# Sheet2.net
KiCad netlist of a schematic drawn in Altium Designer
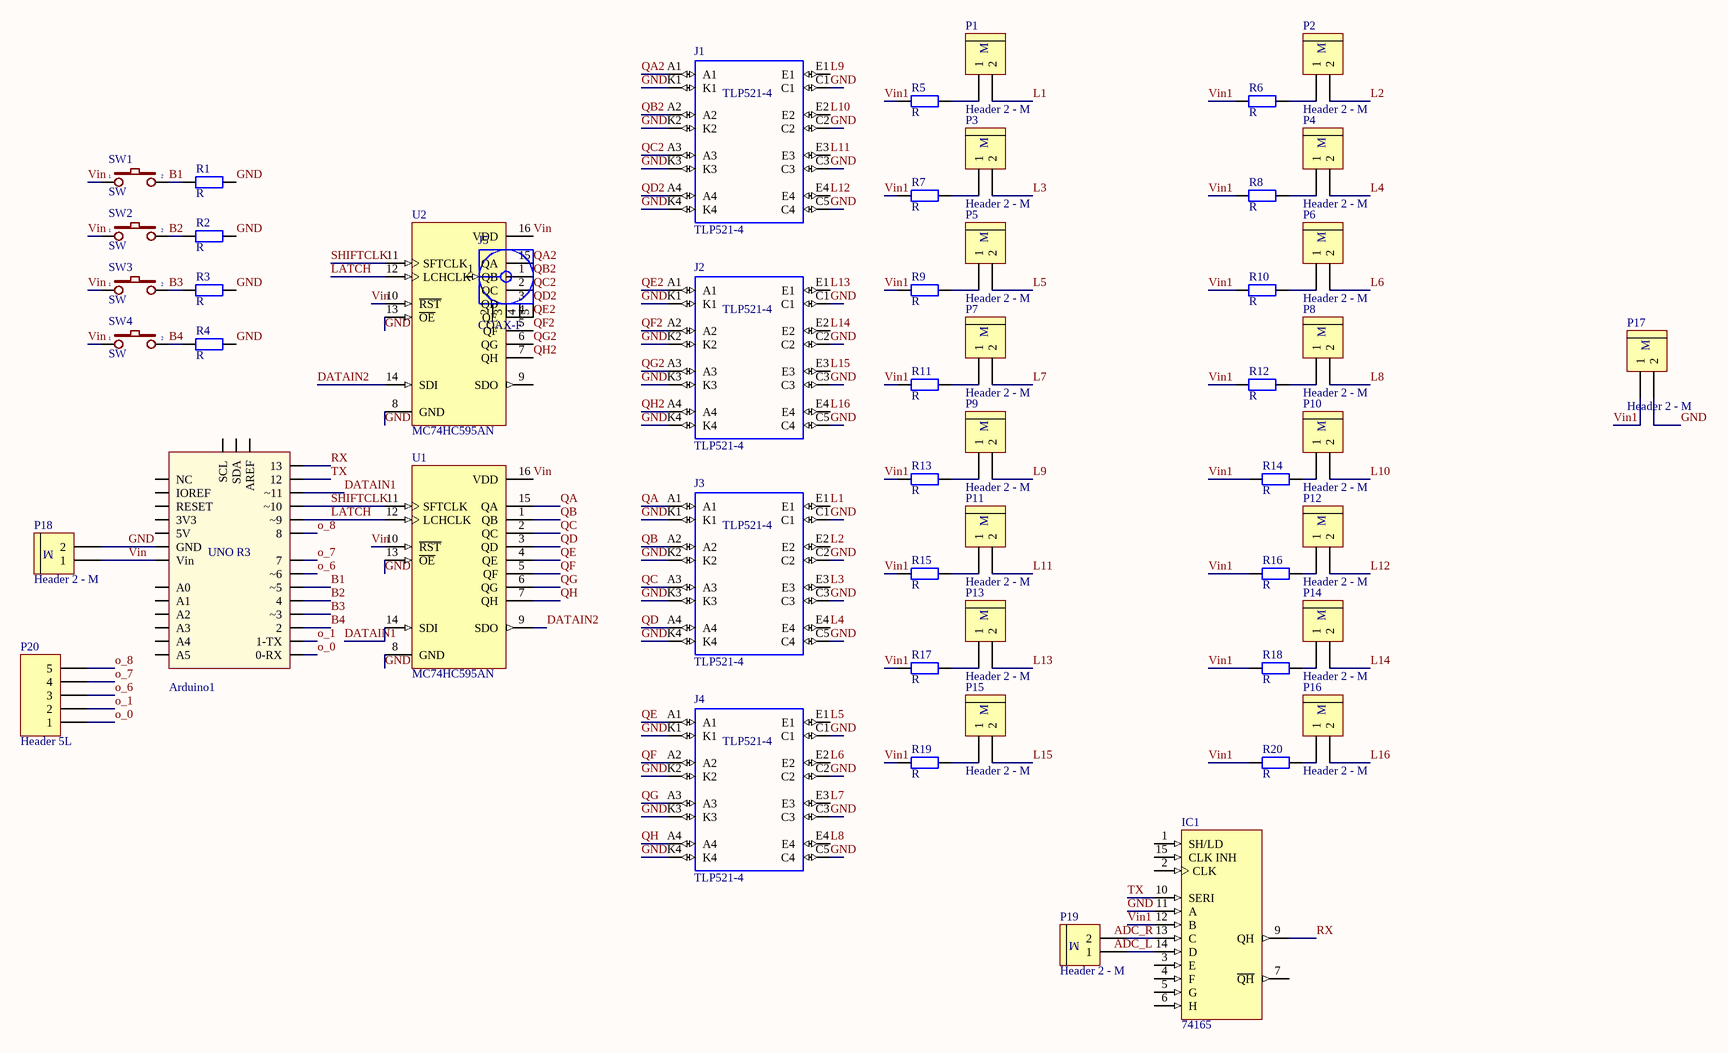
[diagram p0: Sheet2.SchDoc]

(export (version "E")
  (design (tool "Eeschema 10.0.6"))
  (components
    (comp (ref "Arduino1")
      (value "Arduino Uno R3")
      (footprint "Arduino UNO R3")
      (description "Arduino UNO R3")
      (libsource (lib "My Library") (part "Arduino Uno R3"))
    )
    (comp (ref "IC1")
      (value "74165")
      (footprint "DIP16")
      (description "8-Bit Parallel In/Serial Out Shift Register")
      (libsource (lib "adruino") (part "74165"))
    )
    (comp (ref "J1")
      (value "TLP521-4")
      (footprint "TLP521-4_FOOT")
      (description "Optoisolator Transistor Output 5300Vrms 4 Channel 16-DIP")
      (fields (field (name "MF") "Isocom Components") (field (name "DIGI-KEY_PART_NUMBER") "TLP521-4X-ND"))
      (libsource (lib "TLP521-4") (part "TLP521-4"))
    )
    (comp (ref "J2")
      (value "TLP521-4")
      (footprint "TLP521-4_FOOT")
      (description "Optoisolator Transistor Output 5300Vrms 4 Channel 16-DIP")
      (fields (field (name "MF") "Isocom Components") (field (name "DIGI-KEY_PART_NUMBER") "TLP521-4X-ND"))
      (libsource (lib "TLP521-4") (part "TLP521-4"))
    )
    (comp (ref "J3")
      (value "TLP521-4")
      (footprint "TLP521-4_FOOT")
      (description "Optoisolator Transistor Output 5300Vrms 4 Channel 16-DIP")
      (fields (field (name "MF") "Isocom Components") (field (name "DIGI-KEY_PART_NUMBER") "TLP521-4X-ND"))
      (libsource (lib "TLP521-4") (part "TLP521-4"))
    )
    (comp (ref "J4")
      (value "TLP521-4")
      (footprint "TLP521-4_FOOT")
      (description "Optoisolator Transistor Output 5300Vrms 4 Channel 16-DIP")
      (fields (field (name "MF") "Isocom Components") (field (name "DIGI-KEY_PART_NUMBER") "TLP521-4X-ND"))
      (libsource (lib "TLP521-4") (part "TLP521-4"))
    )
    (comp (ref "J5")
      (value "COAX-F")
      (footprint "heromap:MCX5.08-H5")
      (fields (field (name "PUBLISHER") "Altium Limited"))
      (libsource (lib "adruino") (part "COAX-F"))
    )
    (comp (ref "P1")
      (value "Header 2 - M")
      (footprint "Medium - Header 2")
      (description "Header, 2-Pin, Medium")
      (fields (field (name "PUBLISHER") "Altium Limited"))
      (libsource (lib "adruino") (part "Header 2 - M"))
    )
    (comp (ref "P2")
      (value "Header 2 - M")
      (footprint "Medium - Header 2")
      (description "Header, 2-Pin, Medium")
      (fields (field (name "PUBLISHER") "Altium Limited"))
      (libsource (lib "adruino") (part "Header 2 - M"))
    )
    (comp (ref "P3")
      (value "Header 2 - M")
      (footprint "Medium - Header 2")
      (description "Header, 2-Pin, Medium")
      (fields (field (name "PUBLISHER") "Altium Limited"))
      (libsource (lib "adruino") (part "Header 2 - M"))
    )
    (comp (ref "P4")
      (value "Header 2 - M")
      (footprint "Medium - Header 2")
      (description "Header, 2-Pin, Medium")
      (fields (field (name "PUBLISHER") "Altium Limited"))
      (libsource (lib "adruino") (part "Header 2 - M"))
    )
    (comp (ref "P5")
      (value "Header 2 - M")
      (footprint "Medium - Header 2")
      (description "Header, 2-Pin, Medium")
      (fields (field (name "PUBLISHER") "Altium Limited"))
      (libsource (lib "adruino") (part "Header 2 - M"))
    )
    (comp (ref "P6")
      (value "Header 2 - M")
      (footprint "Medium - Header 2")
      (description "Header, 2-Pin, Medium")
      (fields (field (name "PUBLISHER") "Altium Limited"))
      (libsource (lib "adruino") (part "Header 2 - M"))
    )
    (comp (ref "P7")
      (value "Header 2 - M")
      (footprint "Medium - Header 2")
      (description "Header, 2-Pin, Medium")
      (fields (field (name "PUBLISHER") "Altium Limited"))
      (libsource (lib "adruino") (part "Header 2 - M"))
    )
    (comp (ref "P8")
      (value "Header 2 - M")
      (footprint "Medium - Header 2")
      (description "Header, 2-Pin, Medium")
      (fields (field (name "PUBLISHER") "Altium Limited"))
      (libsource (lib "adruino") (part "Header 2 - M"))
    )
    (comp (ref "P9")
      (value "Header 2 - M")
      (footprint "Medium - Header 2")
      (description "Header, 2-Pin, Medium")
      (fields (field (name "PUBLISHER") "Altium Limited"))
      (libsource (lib "adruino") (part "Header 2 - M"))
    )
    (comp (ref "P10")
      (value "Header 2 - M")
      (footprint "Medium - Header 2")
      (description "Header, 2-Pin, Medium")
      (fields (field (name "PUBLISHER") "Altium Limited"))
      (libsource (lib "adruino") (part "Header 2 - M"))
    )
    (comp (ref "P11")
      (value "Header 2 - M")
      (footprint "Medium - Header 2")
      (description "Header, 2-Pin, Medium")
      (fields (field (name "PUBLISHER") "Altium Limited"))
      (libsource (lib "adruino") (part "Header 2 - M"))
    )
    (comp (ref "P12")
      (value "Header 2 - M")
      (footprint "Medium - Header 2")
      (description "Header, 2-Pin, Medium")
      (fields (field (name "PUBLISHER") "Altium Limited"))
      (libsource (lib "adruino") (part "Header 2 - M"))
    )
    (comp (ref "P13")
      (value "Header 2 - M")
      (footprint "Medium - Header 2")
      (description "Header, 2-Pin, Medium")
      (fields (field (name "PUBLISHER") "Altium Limited"))
      (libsource (lib "adruino") (part "Header 2 - M"))
    )
    (comp (ref "P14")
      (value "Header 2 - M")
      (footprint "Medium - Header 2")
      (description "Header, 2-Pin, Medium")
      (fields (field (name "PUBLISHER") "Altium Limited"))
      (libsource (lib "adruino") (part "Header 2 - M"))
    )
    (comp (ref "P15")
      (value "Header 2 - M")
      (footprint "Medium - Header 2")
      (description "Header, 2-Pin, Medium")
      (fields (field (name "PUBLISHER") "Altium Limited"))
      (libsource (lib "adruino") (part "Header 2 - M"))
    )
    (comp (ref "P16")
      (value "Header 2 - M")
      (footprint "Medium - Header 2")
      (description "Header, 2-Pin, Medium")
      (fields (field (name "PUBLISHER") "Altium Limited"))
      (libsource (lib "adruino") (part "Header 2 - M"))
    )
    (comp (ref "P17")
      (value "Header 2 - M")
      (footprint "Medium - Header 2")
      (description "Header, 2-Pin, Medium")
      (fields (field (name "PUBLISHER") "Altium Limited"))
      (libsource (lib "adruino") (part "Header 2 - M"))
    )
    (comp (ref "P18")
      (value "Header 2 - M")
      (footprint "Medium - Header 2")
      (description "Header, 2-Pin, Medium")
      (fields (field (name "PUBLISHER") "Altium Limited"))
      (libsource (lib "") (part "Header 2 - M_1"))
    )
    (comp (ref "P19")
      (value "Header 2 - M")
      (footprint "Medium - Header 2")
      (description "Header, 2-Pin, Medium")
      (fields (field (name "PUBLISHER") "Altium Limited"))
      (libsource (lib "") (part "Header 2 - M_1"))
    )
    (comp (ref "P20")
      (value "Header 5L")
      (footprint "HDR1X5 - L")
      (description "Header, 5-Pin")
      (fields (field (name "PUBLISHER") "Altium Limited"))
      (libsource (lib "adruino") (part "Header 5L"))
    )
    (comp (ref "R1")
      (value "R")
      (footprint "DIEN TRO 1/4 W")
      (description "Resistor")
      (fields (field (name "Comment") "R0.4W") (field (name "PUBLISHER") "Altium Limited"))
      (libsource (lib "adruino") (part "Res 1/4 W"))
    )
    (comp (ref "R2")
      (value "R")
      (footprint "DIEN TRO 1/4 W")
      (description "Resistor")
      (fields (field (name "Comment") "R0.4W") (field (name "PUBLISHER") "Altium Limited"))
      (libsource (lib "adruino") (part "Res 1/4 W"))
    )
    (comp (ref "R3")
      (value "R")
      (footprint "DIEN TRO 1/4 W")
      (description "Resistor")
      (fields (field (name "Comment") "R0.4W") (field (name "PUBLISHER") "Altium Limited"))
      (libsource (lib "adruino") (part "Res 1/4 W"))
    )
    (comp (ref "R4")
      (value "R")
      (footprint "DIEN TRO 1/4 W")
      (description "Resistor")
      (fields (field (name "Comment") "R0.4W") (field (name "PUBLISHER") "Altium Limited"))
      (libsource (lib "adruino") (part "Res 1/4 W"))
    )
    (comp (ref "R5")
      (value "R")
      (footprint "DIEN TRO 1/4 W")
      (description "Resistor")
      (fields (field (name "Comment") "R0.4W") (field (name "PUBLISHER") "Altium Limited"))
      (libsource (lib "adruino") (part "Res 1/4 W"))
    )
    (comp (ref "R6")
      (value "R")
      (footprint "DIEN TRO 1/4 W")
      (description "Resistor")
      (fields (field (name "Comment") "R0.4W") (field (name "PUBLISHER") "Altium Limited"))
      (libsource (lib "adruino") (part "Res 1/4 W"))
    )
    (comp (ref "R7")
      (value "R")
      (footprint "DIEN TRO 1/4 W")
      (description "Resistor")
      (fields (field (name "Comment") "R0.4W") (field (name "PUBLISHER") "Altium Limited"))
      (libsource (lib "adruino") (part "Res 1/4 W"))
    )
    (comp (ref "R8")
      (value "R")
      (footprint "DIEN TRO 1/4 W")
      (description "Resistor")
      (fields (field (name "Comment") "R0.4W") (field (name "PUBLISHER") "Altium Limited"))
      (libsource (lib "adruino") (part "Res 1/4 W"))
    )
    (comp (ref "R9")
      (value "R")
      (footprint "DIEN TRO 1/4 W")
      (description "Resistor")
      (fields (field (name "Comment") "R0.4W") (field (name "PUBLISHER") "Altium Limited"))
      (libsource (lib "adruino") (part "Res 1/4 W"))
    )
    (comp (ref "R10")
      (value "R")
      (footprint "DIEN TRO 1/4 W")
      (description "Resistor")
      (fields (field (name "Comment") "R0.4W") (field (name "PUBLISHER") "Altium Limited"))
      (libsource (lib "adruino") (part "Res 1/4 W"))
    )
    (comp (ref "R11")
      (value "R")
      (footprint "DIEN TRO 1/4 W")
      (description "Resistor")
      (fields (field (name "Comment") "R0.4W") (field (name "PUBLISHER") "Altium Limited"))
      (libsource (lib "adruino") (part "Res 1/4 W"))
    )
    (comp (ref "R12")
      (value "R")
      (footprint "DIEN TRO 1/4 W")
      (description "Resistor")
      (fields (field (name "Comment") "R0.4W") (field (name "PUBLISHER") "Altium Limited"))
      (libsource (lib "adruino") (part "Res 1/4 W"))
    )
    (comp (ref "R13")
      (value "R")
      (footprint "DIEN TRO 1/4 W")
      (description "Resistor")
      (fields (field (name "Comment") "R0.4W") (field (name "PUBLISHER") "Altium Limited"))
      (libsource (lib "adruino") (part "Res 1/4 W"))
    )
    (comp (ref "R14")
      (value "R")
      (footprint "DIEN TRO 1/4 W")
      (description "Resistor")
      (fields (field (name "Comment") "R0.4W") (field (name "PUBLISHER") "Altium Limited"))
      (libsource (lib "adruino") (part "Res 1/4 W"))
    )
    (comp (ref "R15")
      (value "R")
      (footprint "DIEN TRO 1/4 W")
      (description "Resistor")
      (fields (field (name "Comment") "R0.4W") (field (name "PUBLISHER") "Altium Limited"))
      (libsource (lib "adruino") (part "Res 1/4 W"))
    )
    (comp (ref "R16")
      (value "R")
      (footprint "DIEN TRO 1/4 W")
      (description "Resistor")
      (fields (field (name "Comment") "R0.4W") (field (name "PUBLISHER") "Altium Limited"))
      (libsource (lib "adruino") (part "Res 1/4 W"))
    )
    (comp (ref "R17")
      (value "R")
      (footprint "DIEN TRO 1/4 W")
      (description "Resistor")
      (fields (field (name "Comment") "R0.4W") (field (name "PUBLISHER") "Altium Limited"))
      (libsource (lib "adruino") (part "Res 1/4 W"))
    )
    (comp (ref "R18")
      (value "R")
      (footprint "DIEN TRO 1/4 W")
      (description "Resistor")
      (fields (field (name "Comment") "R0.4W") (field (name "PUBLISHER") "Altium Limited"))
      (libsource (lib "adruino") (part "Res 1/4 W"))
    )
    (comp (ref "R19")
      (value "R")
      (footprint "DIEN TRO 1/4 W")
      (description "Resistor")
      (fields (field (name "Comment") "R0.4W") (field (name "PUBLISHER") "Altium Limited"))
      (libsource (lib "adruino") (part "Res 1/4 W"))
    )
    (comp (ref "R20")
      (value "R")
      (footprint "DIEN TRO 1/4 W")
      (description "Resistor")
      (fields (field (name "Comment") "R0.4W") (field (name "PUBLISHER") "Altium Limited"))
      (libsource (lib "adruino") (part "Res 1/4 W"))
    )
    (comp (ref "SW1")
      (value "SW")
      (footprint "SW2")
      (description "Switch button 2 pin")
      (libsource (lib "adruino") (part "SW2"))
    )
    (comp (ref "SW2")
      (value "SW")
      (footprint "SW2")
      (description "Switch button 2 pin")
      (libsource (lib "adruino") (part "SW2"))
    )
    (comp (ref "SW3")
      (value "SW")
      (footprint "SW2")
      (description "Switch button 2 pin")
      (libsource (lib "adruino") (part "SW2"))
    )
    (comp (ref "SW4")
      (value "SW")
      (footprint "SW2")
      (description "Switch button 2 pin")
      (libsource (lib "adruino") (part "SW2"))
    )
    (comp (ref "U1")
      (value "MC74HC595AN")
      (footprint "DIP.100/16/W.300/L.900")
      (description "8-Bit Serial-Input/Serial or Prallel-Output Shift Register with Latched 3-State Outputs")
      (fields (field (name "PUBLISHER") "Altium Limited"))
      (libsource (lib "adruino") (part "MC74HC595AN"))
    )
    (comp (ref "U2")
      (value "MC74HC595AN")
      (footprint "DIP.100/16/W.300/L.900")
      (description "8-Bit Serial-Input/Serial or Prallel-Output Shift Register with Latched 3-State Outputs")
      (fields (field (name "PUBLISHER") "Altium Limited"))
      (libsource (lib "adruino") (part "MC74HC595AN"))
    )
  )
  (nets
    (net (code "3") (name "/B1") (class "Default")
      (node (ref "Arduino1") (pin "~5") (pinfunction "~5_~5") (pintype "passive"))
      (node (ref "R1") (pin "1") (pinfunction "1_1") (pintype "passive"))
      (node (ref "SW1") (pin "2") (pinfunction "2_2") (pintype "passive"))
    )
    (net (code "4") (name "/B2") (class "Default")
      (node (ref "Arduino1") (pin "4") (pinfunction "4_4") (pintype "passive"))
      (node (ref "R2") (pin "1") (pinfunction "1_1") (pintype "passive"))
      (node (ref "SW2") (pin "2") (pinfunction "2_2") (pintype "passive"))
    )
    (net (code "5") (name "/B3") (class "Default")
      (node (ref "Arduino1") (pin "~3") (pinfunction "~3_~3") (pintype "passive"))
      (node (ref "R3") (pin "1") (pinfunction "1_1") (pintype "passive"))
      (node (ref "SW3") (pin "2") (pinfunction "2_2") (pintype "passive"))
    )
    (net (code "6") (name "/B4") (class "Default")
      (node (ref "Arduino1") (pin "2") (pinfunction "2_2") (pintype "passive"))
      (node (ref "R4") (pin "1") (pinfunction "1_1") (pintype "passive"))
      (node (ref "SW4") (pin "2") (pinfunction "2_2") (pintype "passive"))
    )
    (net (code "7") (name "/DATAIN1") (class "Default")
      (node (ref "Arduino1") (pin "~11") (pinfunction "~11_~11") (pintype "passive"))
      (node (ref "U1") (pin "14") (pinfunction "SDI_14") (pintype "input"))
    )
    (net (code "8") (name "/DATAIN2") (class "Default")
      (node (ref "U1") (pin "9") (pinfunction "SDO_9") (pintype "output"))
      (node (ref "U2") (pin "14") (pinfunction "SDI_14") (pintype "input"))
    )
    (net (code "9") (name "/L1") (class "Default")
      (node (ref "J3") (pin "E1") (pinfunction "E1_E1") (pintype "bidirectional"))
      (node (ref "P1") (pin "2") (pinfunction "2_2") (pintype "passive"))
    )
    (net (code "10") (name "/L2") (class "Default")
      (node (ref "J3") (pin "E2") (pinfunction "E2_E2") (pintype "bidirectional"))
      (node (ref "P2") (pin "2") (pinfunction "2_2") (pintype "passive"))
    )
    (net (code "11") (name "/L3") (class "Default")
      (node (ref "J3") (pin "E3") (pinfunction "E3_E3") (pintype "bidirectional"))
      (node (ref "P3") (pin "2") (pinfunction "2_2") (pintype "passive"))
    )
    (net (code "12") (name "/L4") (class "Default")
      (node (ref "J3") (pin "E4") (pinfunction "E4_E4") (pintype "bidirectional"))
      (node (ref "P4") (pin "2") (pinfunction "2_2") (pintype "passive"))
    )
    (net (code "13") (name "/L5") (class "Default")
      (node (ref "J4") (pin "E1") (pinfunction "E1_E1") (pintype "bidirectional"))
      (node (ref "P5") (pin "2") (pinfunction "2_2") (pintype "passive"))
    )
    (net (code "14") (name "/L6") (class "Default")
      (node (ref "J4") (pin "E2") (pinfunction "E2_E2") (pintype "bidirectional"))
      (node (ref "P6") (pin "2") (pinfunction "2_2") (pintype "passive"))
    )
    (net (code "15") (name "/L7") (class "Default")
      (node (ref "J4") (pin "E3") (pinfunction "E3_E3") (pintype "bidirectional"))
      (node (ref "P7") (pin "2") (pinfunction "2_2") (pintype "passive"))
    )
    (net (code "16") (name "/L8") (class "Default")
      (node (ref "J4") (pin "E4") (pinfunction "E4_E4") (pintype "bidirectional"))
      (node (ref "P8") (pin "2") (pinfunction "2_2") (pintype "passive"))
    )
    (net (code "17") (name "/L9") (class "Default")
      (node (ref "J1") (pin "E1") (pinfunction "E1_E1") (pintype "bidirectional"))
      (node (ref "P9") (pin "2") (pinfunction "2_2") (pintype "passive"))
    )
    (net (code "18") (name "/L10") (class "Default")
      (node (ref "J1") (pin "E2") (pinfunction "E2_E2") (pintype "bidirectional"))
      (node (ref "P10") (pin "2") (pinfunction "2_2") (pintype "passive"))
    )
    (net (code "19") (name "/L11") (class "Default")
      (node (ref "J1") (pin "E3") (pinfunction "E3_E3") (pintype "bidirectional"))
      (node (ref "P11") (pin "2") (pinfunction "2_2") (pintype "passive"))
    )
    (net (code "20") (name "/L12") (class "Default")
      (node (ref "J1") (pin "E4") (pinfunction "E4_E4") (pintype "bidirectional"))
      (node (ref "P12") (pin "2") (pinfunction "2_2") (pintype "passive"))
    )
    (net (code "21") (name "/L13") (class "Default")
      (node (ref "J2") (pin "E1") (pinfunction "E1_E1") (pintype "bidirectional"))
      (node (ref "P13") (pin "2") (pinfunction "2_2") (pintype "passive"))
    )
    (net (code "22") (name "/L14") (class "Default")
      (node (ref "J2") (pin "E2") (pinfunction "E2_E2") (pintype "bidirectional"))
      (node (ref "P14") (pin "2") (pinfunction "2_2") (pintype "passive"))
    )
    (net (code "23") (name "/L15") (class "Default")
      (node (ref "J2") (pin "E3") (pinfunction "E3_E3") (pintype "bidirectional"))
      (node (ref "P15") (pin "2") (pinfunction "2_2") (pintype "passive"))
    )
    (net (code "24") (name "/L16") (class "Default")
      (node (ref "J2") (pin "E4") (pinfunction "E4_E4") (pintype "bidirectional"))
      (node (ref "P16") (pin "2") (pinfunction "2_2") (pintype "passive"))
    )
    (net (code "25") (name "/LATCH") (class "Default")
      (node (ref "Arduino1") (pin "~9") (pinfunction "~9_~9") (pintype "passive"))
      (node (ref "U1") (pin "12") (pinfunction "LCHCLK_12") (pintype "input"))
      (node (ref "U2") (pin "12") (pinfunction "LCHCLK_12") (pintype "input"))
    )
    (net (code "26") (name "/QA") (class "Default")
      (node (ref "J3") (pin "A1") (pinfunction "A1_A1") (pintype "bidirectional"))
      (node (ref "U1") (pin "15") (pinfunction "QA_15") (pintype "tri_state"))
    )
    (net (code "27") (name "/QA2") (class "Default")
      (node (ref "J1") (pin "A1") (pinfunction "A1_A1") (pintype "bidirectional"))
      (node (ref "U2") (pin "15") (pinfunction "QA_15") (pintype "tri_state"))
    )
    (net (code "28") (name "/QB") (class "Default")
      (node (ref "J3") (pin "A2") (pinfunction "A2_A2") (pintype "bidirectional"))
      (node (ref "U1") (pin "1") (pinfunction "QB_1") (pintype "tri_state"))
    )
    (net (code "29") (name "/QB2") (class "Default")
      (node (ref "J1") (pin "A2") (pinfunction "A2_A2") (pintype "bidirectional"))
      (node (ref "U2") (pin "1") (pinfunction "QB_1") (pintype "tri_state"))
    )
    (net (code "30") (name "/QC") (class "Default")
      (node (ref "J3") (pin "A3") (pinfunction "A3_A3") (pintype "bidirectional"))
      (node (ref "U1") (pin "2") (pinfunction "QC_2") (pintype "tri_state"))
    )
    (net (code "31") (name "/QC2") (class "Default")
      (node (ref "J1") (pin "A3") (pinfunction "A3_A3") (pintype "bidirectional"))
      (node (ref "U2") (pin "2") (pinfunction "QC_2") (pintype "tri_state"))
    )
    (net (code "32") (name "/QD") (class "Default")
      (node (ref "J3") (pin "A4") (pinfunction "A4_A4") (pintype "bidirectional"))
      (node (ref "U1") (pin "3") (pinfunction "QD_3") (pintype "tri_state"))
    )
    (net (code "33") (name "/QD2") (class "Default")
      (node (ref "J1") (pin "A4") (pinfunction "A4_A4") (pintype "bidirectional"))
      (node (ref "U2") (pin "3") (pinfunction "QD_3") (pintype "tri_state"))
    )
    (net (code "34") (name "/QE") (class "Default")
      (node (ref "J4") (pin "A1") (pinfunction "A1_A1") (pintype "bidirectional"))
      (node (ref "U1") (pin "4") (pinfunction "QE_4") (pintype "tri_state"))
    )
    (net (code "35") (name "/QE2") (class "Default")
      (node (ref "J2") (pin "A1") (pinfunction "A1_A1") (pintype "bidirectional"))
      (node (ref "J5") (pin "5") (pinfunction "GND_5") (pintype "power_in"))
      (node (ref "U2") (pin "4") (pinfunction "QE_4") (pintype "tri_state"))
    )
    (net (code "36") (name "/QF") (class "Default")
      (node (ref "J4") (pin "A2") (pinfunction "A2_A2") (pintype "bidirectional"))
      (node (ref "U1") (pin "5") (pinfunction "QF_5") (pintype "tri_state"))
    )
    (net (code "37") (name "/QF2") (class "Default")
      (node (ref "J2") (pin "A2") (pinfunction "A2_A2") (pintype "bidirectional"))
      (node (ref "U2") (pin "5") (pinfunction "QF_5") (pintype "tri_state"))
    )
    (net (code "38") (name "/QG") (class "Default")
      (node (ref "J4") (pin "A3") (pinfunction "A3_A3") (pintype "bidirectional"))
      (node (ref "U1") (pin "6") (pinfunction "QG_6") (pintype "tri_state"))
    )
    (net (code "39") (name "/QG2") (class "Default")
      (node (ref "J2") (pin "A3") (pinfunction "A3_A3") (pintype "bidirectional"))
      (node (ref "U2") (pin "6") (pinfunction "QG_6") (pintype "tri_state"))
    )
    (net (code "40") (name "/QH") (class "Default")
      (node (ref "J4") (pin "A4") (pinfunction "A4_A4") (pintype "bidirectional"))
      (node (ref "U1") (pin "7") (pinfunction "QH_7") (pintype "tri_state"))
    )
    (net (code "41") (name "/QH2") (class "Default")
      (node (ref "J2") (pin "A4") (pinfunction "A4_A4") (pintype "bidirectional"))
      (node (ref "U2") (pin "7") (pinfunction "QH_7") (pintype "tri_state"))
    )
    (net (code "42") (name "/RX") (class "Default")
      (node (ref "Arduino1") (pin "13") (pinfunction "13_13") (pintype "passive"))
      (node (ref "IC1") (pin "9") (pinfunction "QH_9") (pintype "output"))
    )
    (net (code "43") (name "/SHIFTCLK") (class "Default")
      (node (ref "Arduino1") (pin "~10") (pinfunction "~10_~10") (pintype "passive"))
      (node (ref "U1") (pin "11") (pinfunction "SFTCLK_11") (pintype "input"))
      (node (ref "U2") (pin "11") (pinfunction "SFTCLK_11") (pintype "input"))
    )
    (net (code "44") (name "/TX") (class "Default")
      (node (ref "Arduino1") (pin "12") (pinfunction "12_12") (pintype "passive"))
      (node (ref "IC1") (pin "10") (pinfunction "SERI_10") (pintype "input"))
    )
    (net (code "45") (name "/Vin") (class "Default")
      (node (ref "Arduino1") (pin "Vin") (pinfunction "Vin_Vin") (pintype "passive"))
      (node (ref "P18") (pin "1") (pinfunction "1_1") (pintype "passive"))
      (node (ref "SW1") (pin "1") (pinfunction "1_1") (pintype "passive"))
      (node (ref "SW2") (pin "1") (pinfunction "1_1") (pintype "passive"))
      (node (ref "SW3") (pin "1") (pinfunction "1_1") (pintype "passive"))
      (node (ref "SW4") (pin "1") (pinfunction "1_1") (pintype "passive"))
      (node (ref "U1") (pin "10") (pinfunction "~{RST}_10") (pintype "input"))
      (node (ref "U1") (pin "16") (pinfunction "VDD_16") (pintype "power_in"))
      (node (ref "U2") (pin "10") (pinfunction "~{RST}_10") (pintype "input"))
      (node (ref "U2") (pin "16") (pinfunction "VDD_16") (pintype "power_in"))
    )
    (net (code "46") (name "/Vin1") (class "Default")
      (node (ref "IC1") (pin "12") (pinfunction "B_12") (pintype "input"))
      (node (ref "P17") (pin "1") (pinfunction "1_1") (pintype "passive"))
      (node (ref "R10") (pin "1") (pinfunction "1_1") (pintype "passive"))
      (node (ref "R11") (pin "1") (pinfunction "1_1") (pintype "passive"))
      (node (ref "R12") (pin "1") (pinfunction "1_1") (pintype "passive"))
      (node (ref "R13") (pin "1") (pinfunction "1_1") (pintype "passive"))
      (node (ref "R14") (pin "1") (pinfunction "1_1") (pintype "passive"))
      (node (ref "R15") (pin "1") (pinfunction "1_1") (pintype "passive"))
      (node (ref "R16") (pin "1") (pinfunction "1_1") (pintype "passive"))
      (node (ref "R17") (pin "1") (pinfunction "1_1") (pintype "passive"))
      (node (ref "R18") (pin "1") (pinfunction "1_1") (pintype "passive"))
      (node (ref "R19") (pin "1") (pinfunction "1_1") (pintype "passive"))
      (node (ref "R20") (pin "1") (pinfunction "1_1") (pintype "passive"))
      (node (ref "R5") (pin "1") (pinfunction "1_1") (pintype "passive"))
      (node (ref "R6") (pin "1") (pinfunction "1_1") (pintype "passive"))
      (node (ref "R7") (pin "1") (pinfunction "1_1") (pintype "passive"))
      (node (ref "R8") (pin "1") (pinfunction "1_1") (pintype "passive"))
      (node (ref "R9") (pin "1") (pinfunction "1_1") (pintype "passive"))
    )
    (net (code "47") (name "/o_0") (class "Default")
      (node (ref "Arduino1") (pin "0-RX") (pinfunction "0-RX_0-RX") (pintype "passive"))
      (node (ref "P20") (pin "1") (pinfunction "1_1") (pintype "passive"))
    )
    (net (code "48") (name "/o_1") (class "Default")
      (node (ref "Arduino1") (pin "1-TX") (pinfunction "1-TX_1-TX") (pintype "passive"))
      (node (ref "P20") (pin "2") (pinfunction "2_2") (pintype "passive"))
    )
    (net (code "49") (name "/o_6") (class "Default")
      (node (ref "Arduino1") (pin "~6") (pinfunction "~6_~6") (pintype "passive"))
      (node (ref "P20") (pin "3") (pinfunction "3_3") (pintype "passive"))
    )
    (net (code "50") (name "/o_7") (class "Default")
      (node (ref "Arduino1") (pin "7") (pinfunction "7_7") (pintype "passive"))
      (node (ref "P20") (pin "4") (pinfunction "4_4") (pintype "passive"))
    )
    (net (code "51") (name "/o_8") (class "Default")
      (node (ref "Arduino1") (pin "8") (pinfunction "8_8") (pintype "passive"))
      (node (ref "P20") (pin "5") (pinfunction "5_5") (pintype "passive"))
    )
    (net (code "52") (name "GND") (class "Default")
      (node (ref "Arduino1") (pin "GND") (pinfunction "GND_GND") (pintype "passive"))
      (node (ref "IC1") (pin "11") (pinfunction "A_11") (pintype "input"))
      (node (ref "IC1") (pin "8") (pinfunction "GND_8") (pintype "power_in"))
      (node (ref "J1") (pin "C1") (pinfunction "C1_C1") (pintype "bidirectional"))
      (node (ref "J1") (pin "C2") (pinfunction "C2_C2") (pintype "bidirectional"))
      (node (ref "J1") (pin "C3") (pinfunction "C3_C3") (pintype "bidirectional"))
      (node (ref "J1") (pin "C5") (pinfunction "C4_C5") (pintype "bidirectional"))
      (node (ref "J1") (pin "K1") (pinfunction "K1_K1") (pintype "bidirectional"))
      (node (ref "J1") (pin "K2") (pinfunction "K2_K2") (pintype "bidirectional"))
      (node (ref "J1") (pin "K3") (pinfunction "K3_K3") (pintype "bidirectional"))
      (node (ref "J1") (pin "K4") (pinfunction "K4_K4") (pintype "bidirectional"))
      (node (ref "J2") (pin "C1") (pinfunction "C1_C1") (pintype "bidirectional"))
      (node (ref "J2") (pin "C2") (pinfunction "C2_C2") (pintype "bidirectional"))
      (node (ref "J2") (pin "C3") (pinfunction "C3_C3") (pintype "bidirectional"))
      (node (ref "J2") (pin "C5") (pinfunction "C4_C5") (pintype "bidirectional"))
      (node (ref "J2") (pin "K1") (pinfunction "K1_K1") (pintype "bidirectional"))
      (node (ref "J2") (pin "K2") (pinfunction "K2_K2") (pintype "bidirectional"))
      (node (ref "J2") (pin "K3") (pinfunction "K3_K3") (pintype "bidirectional"))
      (node (ref "J2") (pin "K4") (pinfunction "K4_K4") (pintype "bidirectional"))
      (node (ref "J3") (pin "C1") (pinfunction "C1_C1") (pintype "bidirectional"))
      (node (ref "J3") (pin "C2") (pinfunction "C2_C2") (pintype "bidirectional"))
      (node (ref "J3") (pin "C3") (pinfunction "C3_C3") (pintype "bidirectional"))
      (node (ref "J3") (pin "C5") (pinfunction "C4_C5") (pintype "bidirectional"))
      (node (ref "J3") (pin "K1") (pinfunction "K1_K1") (pintype "bidirectional"))
      (node (ref "J3") (pin "K2") (pinfunction "K2_K2") (pintype "bidirectional"))
      (node (ref "J3") (pin "K3") (pinfunction "K3_K3") (pintype "bidirectional"))
      (node (ref "J3") (pin "K4") (pinfunction "K4_K4") (pintype "bidirectional"))
      (node (ref "J4") (pin "C1") (pinfunction "C1_C1") (pintype "bidirectional"))
      (node (ref "J4") (pin "C2") (pinfunction "C2_C2") (pintype "bidirectional"))
      (node (ref "J4") (pin "C3") (pinfunction "C3_C3") (pintype "bidirectional"))
      (node (ref "J4") (pin "C5") (pinfunction "C4_C5") (pintype "bidirectional"))
      (node (ref "J4") (pin "K1") (pinfunction "K1_K1") (pintype "bidirectional"))
      (node (ref "J4") (pin "K2") (pinfunction "K2_K2") (pintype "bidirectional"))
      (node (ref "J4") (pin "K3") (pinfunction "K3_K3") (pintype "bidirectional"))
      (node (ref "J4") (pin "K4") (pinfunction "K4_K4") (pintype "bidirectional"))
      (node (ref "P17") (pin "2") (pinfunction "2_2") (pintype "passive"))
      (node (ref "P18") (pin "2") (pinfunction "2_2") (pintype "passive"))
      (node (ref "R1") (pin "2") (pinfunction "2_2") (pintype "passive"))
      (node (ref "R2") (pin "2") (pinfunction "2_2") (pintype "passive"))
      (node (ref "R3") (pin "2") (pinfunction "2_2") (pintype "passive"))
      (node (ref "R4") (pin "2") (pinfunction "2_2") (pintype "passive"))
      (node (ref "U1") (pin "13") (pinfunction "~{OE}_13") (pintype "input"))
      (node (ref "U1") (pin "8") (pinfunction "GND_8") (pintype "power_in"))
      (node (ref "U2") (pin "13") (pinfunction "~{OE}_13") (pintype "input"))
      (node (ref "U2") (pin "8") (pinfunction "GND_8") (pintype "power_in"))
    )
    (net (code "53") (name "Net-(IC1-C)") (class "Default")
      (node (ref "IC1") (pin "13") (pinfunction "C_13") (pintype "input"))
      (node (ref "P19") (pin "2") (pinfunction "2_2") (pintype "passive"))
    )
    (net (code "54") (name "Net-(IC1-D)") (class "Default")
      (node (ref "IC1") (pin "14") (pinfunction "D_14") (pintype "input"))
      (node (ref "P19") (pin "1") (pinfunction "1_1") (pintype "passive"))
    )
    (net (code "55") (name "Net-(P1-Pad1)") (class "Default")
      (node (ref "P1") (pin "1") (pinfunction "1_1") (pintype "passive"))
      (node (ref "R5") (pin "2") (pinfunction "2_2") (pintype "passive"))
    )
    (net (code "56") (name "Net-(P2-Pad1)") (class "Default")
      (node (ref "P2") (pin "1") (pinfunction "1_1") (pintype "passive"))
      (node (ref "R6") (pin "2") (pinfunction "2_2") (pintype "passive"))
    )
    (net (code "57") (name "Net-(P3-Pad1)") (class "Default")
      (node (ref "P3") (pin "1") (pinfunction "1_1") (pintype "passive"))
      (node (ref "R7") (pin "2") (pinfunction "2_2") (pintype "passive"))
    )
    (net (code "58") (name "Net-(P4-Pad1)") (class "Default")
      (node (ref "P4") (pin "1") (pinfunction "1_1") (pintype "passive"))
      (node (ref "R8") (pin "2") (pinfunction "2_2") (pintype "passive"))
    )
    (net (code "59") (name "Net-(P5-Pad1)") (class "Default")
      (node (ref "P5") (pin "1") (pinfunction "1_1") (pintype "passive"))
      (node (ref "R9") (pin "2") (pinfunction "2_2") (pintype "passive"))
    )
    (net (code "60") (name "Net-(P6-Pad1)") (class "Default")
      (node (ref "P6") (pin "1") (pinfunction "1_1") (pintype "passive"))
      (node (ref "R10") (pin "2") (pinfunction "2_2") (pintype "passive"))
    )
    (net (code "61") (name "Net-(P7-Pad1)") (class "Default")
      (node (ref "P7") (pin "1") (pinfunction "1_1") (pintype "passive"))
      (node (ref "R11") (pin "2") (pinfunction "2_2") (pintype "passive"))
    )
    (net (code "62") (name "Net-(P8-Pad1)") (class "Default")
      (node (ref "P8") (pin "1") (pinfunction "1_1") (pintype "passive"))
      (node (ref "R12") (pin "2") (pinfunction "2_2") (pintype "passive"))
    )
    (net (code "63") (name "Net-(P9-Pad1)") (class "Default")
      (node (ref "P9") (pin "1") (pinfunction "1_1") (pintype "passive"))
      (node (ref "R13") (pin "2") (pinfunction "2_2") (pintype "passive"))
    )
    (net (code "64") (name "Net-(P10-Pad1)") (class "Default")
      (node (ref "P10") (pin "1") (pinfunction "1_1") (pintype "passive"))
      (node (ref "R14") (pin "2") (pinfunction "2_2") (pintype "passive"))
    )
    (net (code "65") (name "Net-(P11-Pad1)") (class "Default")
      (node (ref "P11") (pin "1") (pinfunction "1_1") (pintype "passive"))
      (node (ref "R15") (pin "2") (pinfunction "2_2") (pintype "passive"))
    )
    (net (code "66") (name "Net-(P12-Pad1)") (class "Default")
      (node (ref "P12") (pin "1") (pinfunction "1_1") (pintype "passive"))
      (node (ref "R16") (pin "2") (pinfunction "2_2") (pintype "passive"))
    )
    (net (code "67") (name "Net-(P13-Pad1)") (class "Default")
      (node (ref "P13") (pin "1") (pinfunction "1_1") (pintype "passive"))
      (node (ref "R17") (pin "2") (pinfunction "2_2") (pintype "passive"))
    )
    (net (code "68") (name "Net-(P14-Pad1)") (class "Default")
      (node (ref "P14") (pin "1") (pinfunction "1_1") (pintype "passive"))
      (node (ref "R18") (pin "2") (pinfunction "2_2") (pintype "passive"))
    )
    (net (code "69") (name "Net-(P15-Pad1)") (class "Default")
      (node (ref "P15") (pin "1") (pinfunction "1_1") (pintype "passive"))
      (node (ref "R19") (pin "2") (pinfunction "2_2") (pintype "passive"))
    )
    (net (code "70") (name "Net-(P16-Pad1)") (class "Default")
      (node (ref "P16") (pin "1") (pinfunction "1_1") (pintype "passive"))
      (node (ref "R20") (pin "2") (pinfunction "2_2") (pintype "passive"))
    )
    (net (code "71") (name "VCC") (class "Default")
      (node (ref "IC1") (pin "16") (pinfunction "VCC_16") (pintype "power_in"))
    )
    (net (code "72") (name "unconnected-(Arduino1-Pad3V3)") (class "Default")
      (node (ref "Arduino1") (pin "3V3") (pinfunction "3V3_3V3") (pintype "passive"))
    )
    (net (code "73") (name "unconnected-(Arduino1-Pad5V)") (class "Default")
      (node (ref "Arduino1") (pin "5V") (pinfunction "5V_5V") (pintype "passive"))
    )
    (net (code "74") (name "unconnected-(Arduino1-PadA0)") (class "Default")
      (node (ref "Arduino1") (pin "A0") (pinfunction "A0_A0") (pintype "passive"))
    )
    (net (code "75") (name "unconnected-(Arduino1-PadA1)") (class "Default")
      (node (ref "Arduino1") (pin "A1") (pinfunction "A1_A1") (pintype "passive"))
    )
    (net (code "76") (name "unconnected-(Arduino1-PadA2)") (class "Default")
      (node (ref "Arduino1") (pin "A2") (pinfunction "A2_A2") (pintype "passive"))
    )
    (net (code "77") (name "unconnected-(Arduino1-PadA3)") (class "Default")
      (node (ref "Arduino1") (pin "A3") (pinfunction "A3_A3") (pintype "passive"))
    )
    (net (code "78") (name "unconnected-(Arduino1-PadA4)") (class "Default")
      (node (ref "Arduino1") (pin "A4") (pinfunction "A4_A4") (pintype "passive"))
    )
    (net (code "79") (name "unconnected-(Arduino1-PadA5)") (class "Default")
      (node (ref "Arduino1") (pin "A5") (pinfunction "A5_A5") (pintype "passive"))
    )
    (net (code "80") (name "unconnected-(Arduino1-PadAREF)") (class "Default")
      (node (ref "Arduino1") (pin "AREF") (pinfunction "AREF_AREF") (pintype "passive"))
    )
    (net (code "81") (name "unconnected-(Arduino1-PadIOREF)") (class "Default")
      (node (ref "Arduino1") (pin "IOREF") (pinfunction "IOREF_IOREF") (pintype "passive"))
    )
    (net (code "82") (name "unconnected-(Arduino1-PadNC)") (class "Default")
      (node (ref "Arduino1") (pin "NC") (pinfunction "NC_NC") (pintype "passive"))
    )
    (net (code "83") (name "unconnected-(Arduino1-PadRESET)") (class "Default")
      (node (ref "Arduino1") (pin "RESET") (pinfunction "RESET_RESET") (pintype "passive"))
    )
    (net (code "84") (name "unconnected-(Arduino1-PadSCL)") (class "Default")
      (node (ref "Arduino1") (pin "SCL") (pinfunction "SCL_SCL") (pintype "passive"))
    )
    (net (code "85") (name "unconnected-(Arduino1-PadSDA)") (class "Default")
      (node (ref "Arduino1") (pin "SDA") (pinfunction "SDA_SDA") (pintype "passive"))
    )
    (net (code "86") (name "unconnected-(IC1-CLK-Pad2)") (class "Default")
      (node (ref "IC1") (pin "2") (pinfunction "CLK_2") (pintype "input"))
    )
    (net (code "87") (name "unconnected-(IC1-CLK_INH-Pad15)") (class "Default")
      (node (ref "IC1") (pin "15") (pinfunction "CLK_INH_15") (pintype "input"))
    )
    (net (code "88") (name "unconnected-(IC1-E-Pad3)") (class "Default")
      (node (ref "IC1") (pin "3") (pinfunction "E_3") (pintype "input"))
    )
    (net (code "89") (name "unconnected-(IC1-F-Pad4)") (class "Default")
      (node (ref "IC1") (pin "4") (pinfunction "F_4") (pintype "input"))
    )
    (net (code "90") (name "unconnected-(IC1-G-Pad5)") (class "Default")
      (node (ref "IC1") (pin "5") (pinfunction "G_5") (pintype "input"))
    )
    (net (code "91") (name "unconnected-(IC1-H-Pad6)") (class "Default")
      (node (ref "IC1") (pin "6") (pinfunction "H_6") (pintype "input"))
    )
    (net (code "92") (name "unconnected-(IC1-SH{slash}LD-Pad1)") (class "Default")
      (node (ref "IC1") (pin "1") (pinfunction "SH/LD_1") (pintype "input"))
    )
    (net (code "93") (name "unconnected-(IC1-~{QH}-Pad7)") (class "Default")
      (node (ref "IC1") (pin "7") (pinfunction "~{QH}_7") (pintype "output"))
    )
    (net (code "94") (name "unconnected-(J5-GND-Pad2)") (class "Default")
      (node (ref "J5") (pin "2") (pinfunction "GND_2") (pintype "power_in"))
    )
    (net (code "95") (name "unconnected-(J5-GND-Pad3)") (class "Default")
      (node (ref "J5") (pin "3") (pinfunction "GND_3") (pintype "power_in"))
    )
    (net (code "96") (name "unconnected-(J5-GND-Pad4)") (class "Default")
      (node (ref "J5") (pin "4") (pinfunction "GND_4") (pintype "power_in"))
    )
    (net (code "97") (name "unconnected-(J5-Signal-Pad1)") (class "Default")
      (node (ref "J5") (pin "1") (pinfunction "Signal_1") (pintype "input"))
    )
    (net (code "98") (name "unconnected-(U2-SDO-Pad9)") (class "Default")
      (node (ref "U2") (pin "9") (pinfunction "SDO_9") (pintype "output"))
    )
  )
)
